# RELAY_02.net
KiCad netlist of a schematic drawn in Altium Designer
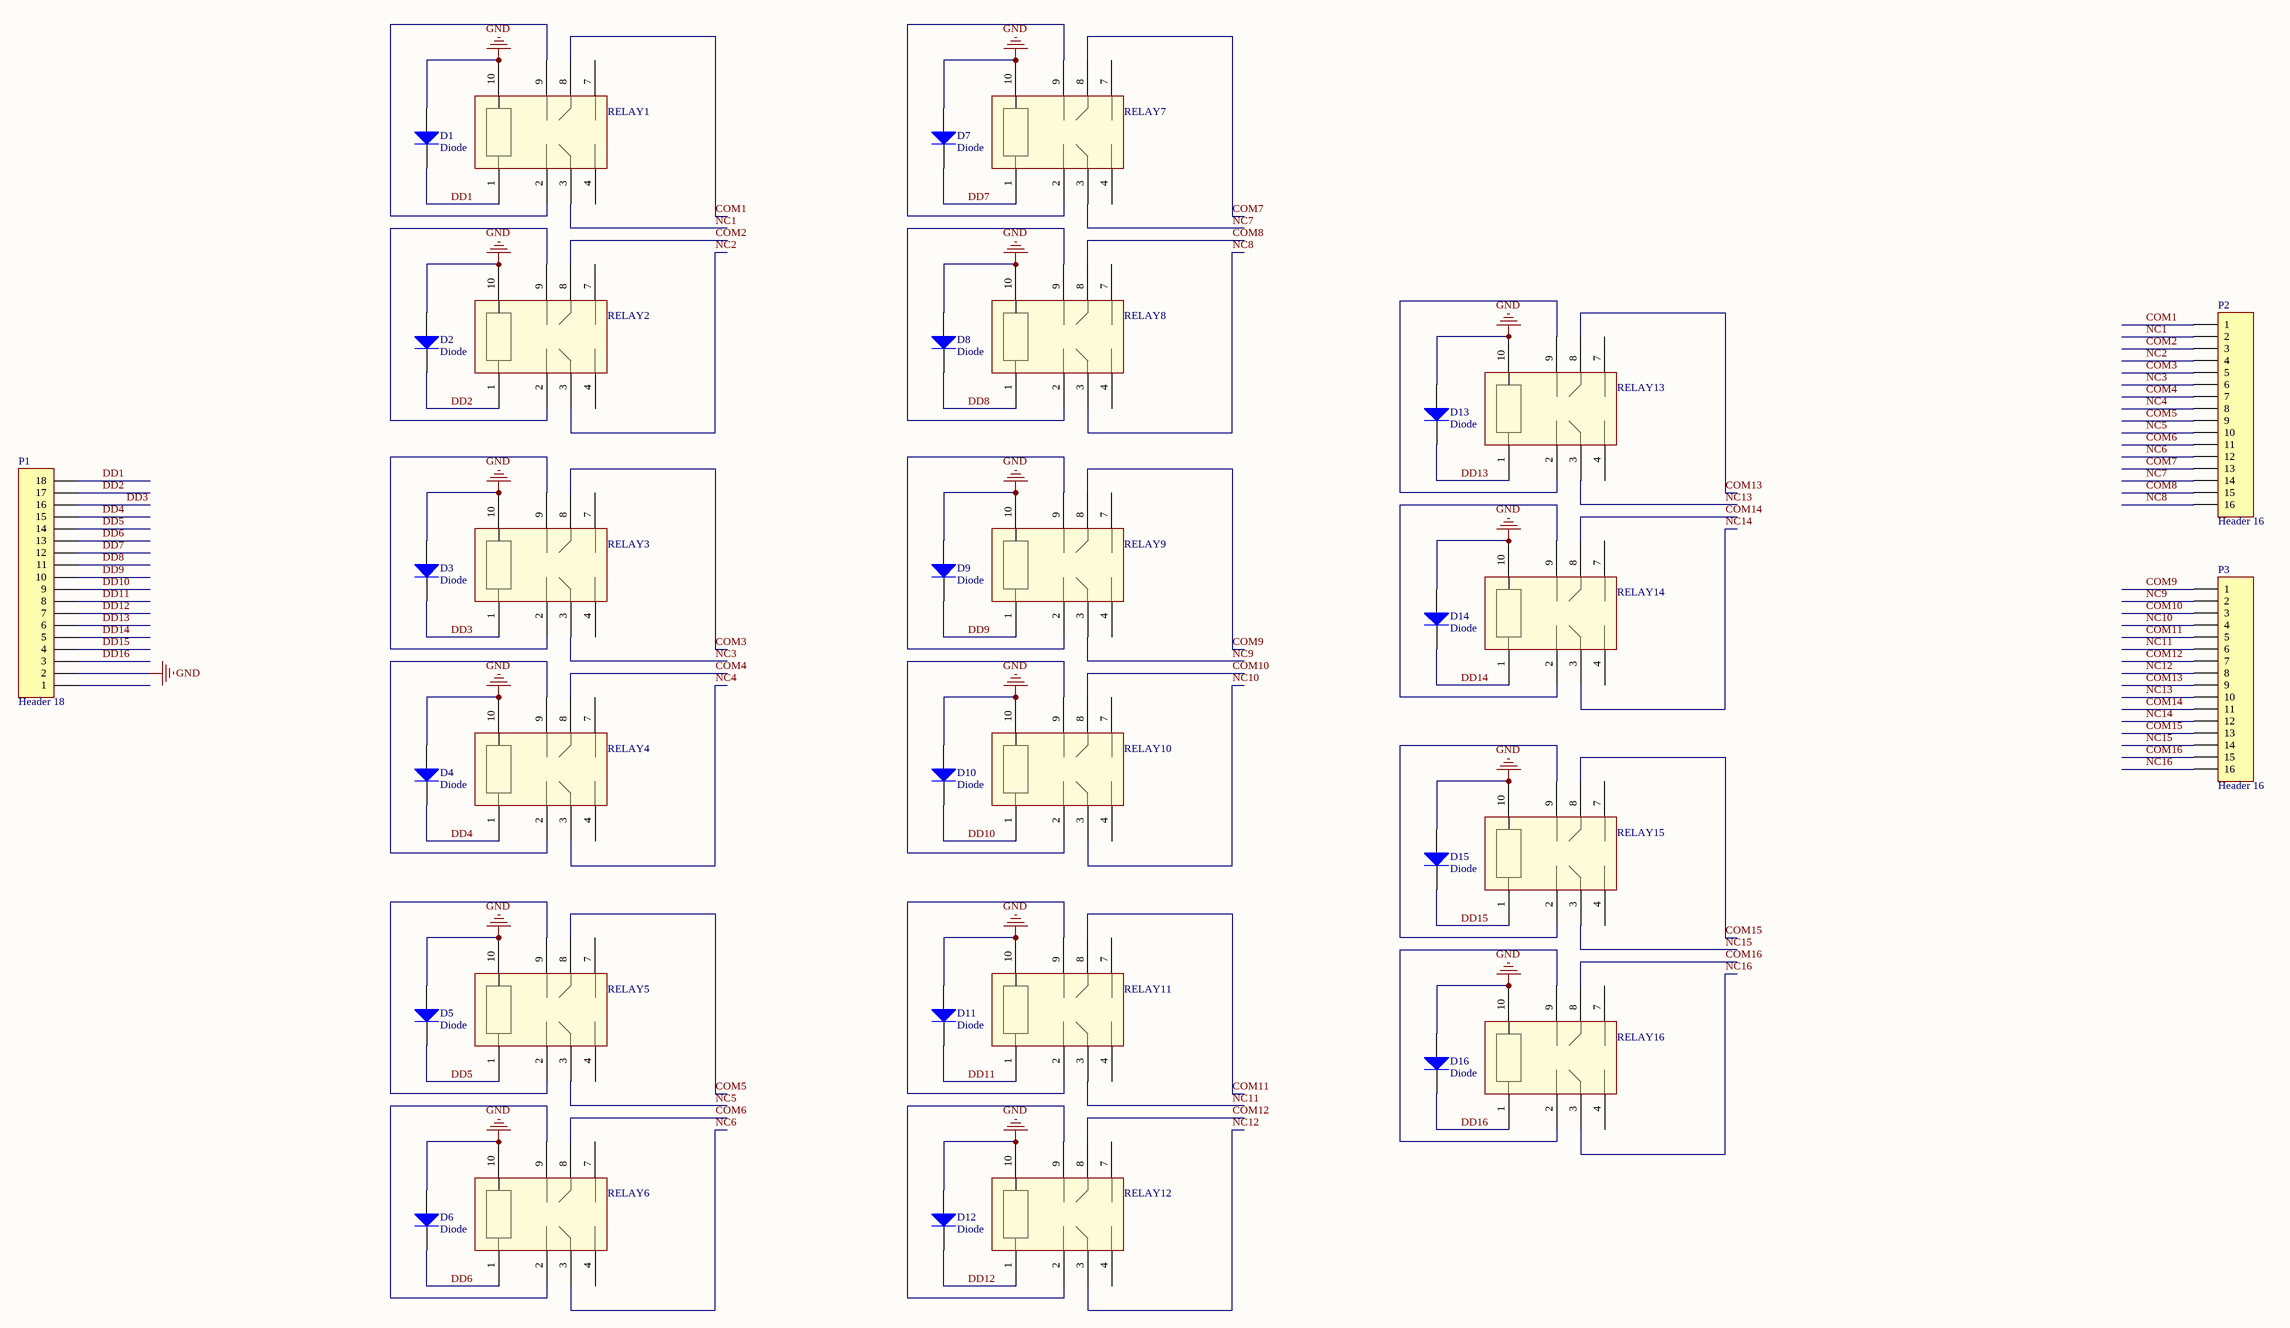
[diagram p0: RELAY 02.SchDoc]

(export (version "E")
  (design (tool "Eeschema 10.0.6"))
  (components
    (comp (ref "D1")
      (value "Diode")
      (footprint "SMB")
      (description "Default Diode")
      (fields (field (name "PUBLISHER") "Altium Limited"))
      (libsource (lib "Miscellaneous Devices") (part "Diode"))
    )
    (comp (ref "D2")
      (value "Diode")
      (footprint "SMB")
      (description "Default Diode")
      (fields (field (name "PUBLISHER") "Altium Limited"))
      (libsource (lib "Miscellaneous Devices") (part "Diode"))
    )
    (comp (ref "D3")
      (value "Diode")
      (footprint "SMB")
      (description "Default Diode")
      (fields (field (name "PUBLISHER") "Altium Limited"))
      (libsource (lib "Miscellaneous Devices") (part "Diode"))
    )
    (comp (ref "D4")
      (value "Diode")
      (footprint "SMB")
      (description "Default Diode")
      (fields (field (name "PUBLISHER") "Altium Limited"))
      (libsource (lib "Miscellaneous Devices") (part "Diode"))
    )
    (comp (ref "D5")
      (value "Diode")
      (footprint "SMB")
      (description "Default Diode")
      (fields (field (name "PUBLISHER") "Altium Limited"))
      (libsource (lib "Miscellaneous Devices") (part "Diode"))
    )
    (comp (ref "D6")
      (value "Diode")
      (footprint "SMB")
      (description "Default Diode")
      (fields (field (name "PUBLISHER") "Altium Limited"))
      (libsource (lib "Miscellaneous Devices") (part "Diode"))
    )
    (comp (ref "D7")
      (value "Diode")
      (footprint "SMB")
      (description "Default Diode")
      (fields (field (name "PUBLISHER") "Altium Limited"))
      (libsource (lib "Miscellaneous Devices") (part "Diode"))
    )
    (comp (ref "D8")
      (value "Diode")
      (footprint "SMB")
      (description "Default Diode")
      (fields (field (name "PUBLISHER") "Altium Limited"))
      (libsource (lib "Miscellaneous Devices") (part "Diode"))
    )
    (comp (ref "D9")
      (value "Diode")
      (footprint "SMB")
      (description "Default Diode")
      (fields (field (name "PUBLISHER") "Altium Limited"))
      (libsource (lib "Miscellaneous Devices") (part "Diode"))
    )
    (comp (ref "D10")
      (value "Diode")
      (footprint "SMB")
      (description "Default Diode")
      (fields (field (name "PUBLISHER") "Altium Limited"))
      (libsource (lib "Miscellaneous Devices") (part "Diode"))
    )
    (comp (ref "D11")
      (value "Diode")
      (footprint "SMB")
      (description "Default Diode")
      (fields (field (name "PUBLISHER") "Altium Limited"))
      (libsource (lib "Miscellaneous Devices") (part "Diode"))
    )
    (comp (ref "D12")
      (value "Diode")
      (footprint "SMB")
      (description "Default Diode")
      (fields (field (name "PUBLISHER") "Altium Limited"))
      (libsource (lib "Miscellaneous Devices") (part "Diode"))
    )
    (comp (ref "D13")
      (value "Diode")
      (footprint "SMB")
      (description "Default Diode")
      (fields (field (name "PUBLISHER") "Altium Limited"))
      (libsource (lib "Miscellaneous Devices") (part "Diode"))
    )
    (comp (ref "D14")
      (value "Diode")
      (footprint "SMB")
      (description "Default Diode")
      (fields (field (name "PUBLISHER") "Altium Limited"))
      (libsource (lib "Miscellaneous Devices") (part "Diode"))
    )
    (comp (ref "D15")
      (value "Diode")
      (footprint "SMB")
      (description "Default Diode")
      (fields (field (name "PUBLISHER") "Altium Limited"))
      (libsource (lib "Miscellaneous Devices") (part "Diode"))
    )
    (comp (ref "D16")
      (value "Diode")
      (footprint "SMB")
      (description "Default Diode")
      (fields (field (name "PUBLISHER") "Altium Limited"))
      (libsource (lib "Miscellaneous Devices") (part "Diode"))
    )
    (comp (ref "P1")
      (value "Header 18")
      (footprint "CON 18")
      (description "Header, 18-Pin")
      (fields (field (name "PUBLISHER") "Altium Limited"))
      (libsource (lib "Miscellaneous Connectors") (part "Header 18"))
    )
    (comp (ref "P2")
      (value "Header 16")
      (footprint "CON 16")
      (description "Header, 16-Pin")
      (fields (field (name "PUBLISHER") "Altium Limited"))
      (libsource (lib "Miscellaneous Connectors") (part "Header 16"))
    )
    (comp (ref "P3")
      (value "Header 16")
      (footprint "CON 16")
      (description "Header, 16-Pin")
      (fields (field (name "PUBLISHER") "Altium Limited"))
      (libsource (lib "Miscellaneous Connectors") (part "Header 16"))
    )
    (comp (ref "RELAY1")
      (value "OMRON RELAY")
      (footprint "G6H-2")
      (libsource (lib "dung_maker_2018") (part "OMRON G6H-2"))
    )
    (comp (ref "RELAY2")
      (value "OMRON RELAY")
      (footprint "G6H-2")
      (libsource (lib "dung_maker_2018") (part "OMRON G6H-2"))
    )
    (comp (ref "RELAY3")
      (value "OMRON RELAY")
      (footprint "G6H-2")
      (libsource (lib "dung_maker_2018") (part "OMRON G6H-2"))
    )
    (comp (ref "RELAY4")
      (value "OMRON RELAY")
      (footprint "G6H-2")
      (libsource (lib "dung_maker_2018") (part "OMRON G6H-2"))
    )
    (comp (ref "RELAY5")
      (value "OMRON RELAY")
      (footprint "G6H-2")
      (libsource (lib "dung_maker_2018") (part "OMRON G6H-2"))
    )
    (comp (ref "RELAY6")
      (value "OMRON RELAY")
      (footprint "G6H-2")
      (libsource (lib "dung_maker_2018") (part "OMRON G6H-2"))
    )
    (comp (ref "RELAY7")
      (value "OMRON RELAY")
      (footprint "G6H-2")
      (libsource (lib "dung_maker_2018") (part "OMRON G6H-2"))
    )
    (comp (ref "RELAY8")
      (value "OMRON RELAY")
      (footprint "G6H-2")
      (libsource (lib "dung_maker_2018") (part "OMRON G6H-2"))
    )
    (comp (ref "RELAY9")
      (value "OMRON RELAY")
      (footprint "G6H-2")
      (libsource (lib "dung_maker_2018") (part "OMRON G6H-2"))
    )
    (comp (ref "RELAY10")
      (value "OMRON RELAY")
      (footprint "G6H-2")
      (libsource (lib "dung_maker_2018") (part "OMRON G6H-2"))
    )
    (comp (ref "RELAY11")
      (value "OMRON RELAY")
      (footprint "G6H-2")
      (libsource (lib "dung_maker_2018") (part "OMRON G6H-2"))
    )
    (comp (ref "RELAY12")
      (value "OMRON RELAY")
      (footprint "G6H-2")
      (libsource (lib "dung_maker_2018") (part "OMRON G6H-2"))
    )
    (comp (ref "RELAY13")
      (value "OMRON RELAY")
      (footprint "G6H-2")
      (libsource (lib "dung_maker_2018") (part "OMRON G6H-2"))
    )
    (comp (ref "RELAY14")
      (value "OMRON RELAY")
      (footprint "G6H-2")
      (libsource (lib "dung_maker_2018") (part "OMRON G6H-2"))
    )
    (comp (ref "RELAY15")
      (value "OMRON RELAY")
      (footprint "G6H-2")
      (libsource (lib "dung_maker_2018") (part "OMRON G6H-2"))
    )
    (comp (ref "RELAY16")
      (value "OMRON RELAY")
      (footprint "G6H-2")
      (libsource (lib "dung_maker_2018") (part "OMRON G6H-2"))
    )
  )
  (nets
    (net (code "1") (name "/COM1") (class "Default")
      (node (ref "P2") (pin "1") (pinfunction "1_1") (pintype "passive"))
      (node (ref "RELAY1") (pin "8") (pinfunction "8_8") (pintype "passive"))
    )
    (net (code "2") (name "/COM2") (class "Default")
      (node (ref "P2") (pin "3") (pinfunction "3_3") (pintype "passive"))
      (node (ref "RELAY2") (pin "8") (pinfunction "8_8") (pintype "passive"))
    )
    (net (code "3") (name "/COM3") (class "Default")
      (node (ref "P2") (pin "5") (pinfunction "5_5") (pintype "passive"))
      (node (ref "RELAY3") (pin "8") (pinfunction "8_8") (pintype "passive"))
    )
    (net (code "4") (name "/COM4") (class "Default")
      (node (ref "P2") (pin "7") (pinfunction "7_7") (pintype "passive"))
      (node (ref "RELAY4") (pin "8") (pinfunction "8_8") (pintype "passive"))
    )
    (net (code "5") (name "/COM5") (class "Default")
      (node (ref "P2") (pin "9") (pinfunction "9_9") (pintype "passive"))
      (node (ref "RELAY5") (pin "8") (pinfunction "8_8") (pintype "passive"))
    )
    (net (code "6") (name "/COM6") (class "Default")
      (node (ref "P2") (pin "11") (pinfunction "11_11") (pintype "passive"))
      (node (ref "RELAY6") (pin "8") (pinfunction "8_8") (pintype "passive"))
    )
    (net (code "7") (name "/COM7") (class "Default")
      (node (ref "P2") (pin "13") (pinfunction "13_13") (pintype "passive"))
      (node (ref "RELAY7") (pin "8") (pinfunction "8_8") (pintype "passive"))
    )
    (net (code "8") (name "/COM8") (class "Default")
      (node (ref "P2") (pin "15") (pinfunction "15_15") (pintype "passive"))
      (node (ref "RELAY8") (pin "8") (pinfunction "8_8") (pintype "passive"))
    )
    (net (code "9") (name "/COM9") (class "Default")
      (node (ref "P3") (pin "1") (pinfunction "1_1") (pintype "passive"))
      (node (ref "RELAY9") (pin "8") (pinfunction "8_8") (pintype "passive"))
    )
    (net (code "10") (name "/COM10") (class "Default")
      (node (ref "P3") (pin "3") (pinfunction "3_3") (pintype "passive"))
      (node (ref "RELAY10") (pin "8") (pinfunction "8_8") (pintype "passive"))
    )
    (net (code "11") (name "/COM11") (class "Default")
      (node (ref "P3") (pin "5") (pinfunction "5_5") (pintype "passive"))
      (node (ref "RELAY11") (pin "8") (pinfunction "8_8") (pintype "passive"))
    )
    (net (code "12") (name "/COM12") (class "Default")
      (node (ref "P3") (pin "7") (pinfunction "7_7") (pintype "passive"))
      (node (ref "RELAY12") (pin "8") (pinfunction "8_8") (pintype "passive"))
    )
    (net (code "13") (name "/COM13") (class "Default")
      (node (ref "P3") (pin "9") (pinfunction "9_9") (pintype "passive"))
      (node (ref "RELAY13") (pin "8") (pinfunction "8_8") (pintype "passive"))
    )
    (net (code "14") (name "/COM14") (class "Default")
      (node (ref "P3") (pin "11") (pinfunction "11_11") (pintype "passive"))
      (node (ref "RELAY14") (pin "8") (pinfunction "8_8") (pintype "passive"))
    )
    (net (code "15") (name "/COM15") (class "Default")
      (node (ref "P3") (pin "13") (pinfunction "13_13") (pintype "passive"))
      (node (ref "RELAY15") (pin "8") (pinfunction "8_8") (pintype "passive"))
    )
    (net (code "16") (name "/COM16") (class "Default")
      (node (ref "P3") (pin "15") (pinfunction "15_15") (pintype "passive"))
      (node (ref "RELAY16") (pin "8") (pinfunction "8_8") (pintype "passive"))
    )
    (net (code "17") (name "/DD1") (class "Default")
      (node (ref "D1") (pin "2") (pinfunction "K_2") (pintype "passive"))
      (node (ref "P1") (pin "18") (pinfunction "18_18") (pintype "passive"))
      (node (ref "RELAY1") (pin "1") (pinfunction "1_1") (pintype "passive"))
    )
    (net (code "18") (name "/DD2") (class "Default")
      (node (ref "D2") (pin "2") (pinfunction "K_2") (pintype "passive"))
      (node (ref "P1") (pin "17") (pinfunction "17_17") (pintype "passive"))
      (node (ref "RELAY2") (pin "1") (pinfunction "1_1") (pintype "passive"))
    )
    (net (code "19") (name "/DD3") (class "Default")
      (node (ref "D3") (pin "2") (pinfunction "K_2") (pintype "passive"))
      (node (ref "P1") (pin "16") (pinfunction "16_16") (pintype "passive"))
      (node (ref "RELAY3") (pin "1") (pinfunction "1_1") (pintype "passive"))
    )
    (net (code "20") (name "/DD4") (class "Default")
      (node (ref "D4") (pin "2") (pinfunction "K_2") (pintype "passive"))
      (node (ref "P1") (pin "15") (pinfunction "15_15") (pintype "passive"))
      (node (ref "RELAY4") (pin "1") (pinfunction "1_1") (pintype "passive"))
    )
    (net (code "21") (name "/DD5") (class "Default")
      (node (ref "D5") (pin "2") (pinfunction "K_2") (pintype "passive"))
      (node (ref "P1") (pin "14") (pinfunction "14_14") (pintype "passive"))
      (node (ref "RELAY5") (pin "1") (pinfunction "1_1") (pintype "passive"))
    )
    (net (code "22") (name "/DD6") (class "Default")
      (node (ref "D6") (pin "2") (pinfunction "K_2") (pintype "passive"))
      (node (ref "P1") (pin "13") (pinfunction "13_13") (pintype "passive"))
      (node (ref "RELAY6") (pin "1") (pinfunction "1_1") (pintype "passive"))
    )
    (net (code "23") (name "/DD7") (class "Default")
      (node (ref "D7") (pin "2") (pinfunction "K_2") (pintype "passive"))
      (node (ref "P1") (pin "12") (pinfunction "12_12") (pintype "passive"))
      (node (ref "RELAY7") (pin "1") (pinfunction "1_1") (pintype "passive"))
    )
    (net (code "24") (name "/DD8") (class "Default")
      (node (ref "D8") (pin "2") (pinfunction "K_2") (pintype "passive"))
      (node (ref "P1") (pin "11") (pinfunction "11_11") (pintype "passive"))
      (node (ref "RELAY8") (pin "1") (pinfunction "1_1") (pintype "passive"))
    )
    (net (code "25") (name "/DD9") (class "Default")
      (node (ref "D9") (pin "2") (pinfunction "K_2") (pintype "passive"))
      (node (ref "P1") (pin "10") (pinfunction "10_10") (pintype "passive"))
      (node (ref "RELAY9") (pin "1") (pinfunction "1_1") (pintype "passive"))
    )
    (net (code "26") (name "/DD10") (class "Default")
      (node (ref "D10") (pin "2") (pinfunction "K_2") (pintype "passive"))
      (node (ref "P1") (pin "9") (pinfunction "9_9") (pintype "passive"))
      (node (ref "RELAY10") (pin "1") (pinfunction "1_1") (pintype "passive"))
    )
    (net (code "27") (name "/DD11") (class "Default")
      (node (ref "D11") (pin "2") (pinfunction "K_2") (pintype "passive"))
      (node (ref "P1") (pin "8") (pinfunction "8_8") (pintype "passive"))
      (node (ref "RELAY11") (pin "1") (pinfunction "1_1") (pintype "passive"))
    )
    (net (code "28") (name "/DD12") (class "Default")
      (node (ref "D12") (pin "2") (pinfunction "K_2") (pintype "passive"))
      (node (ref "P1") (pin "7") (pinfunction "7_7") (pintype "passive"))
      (node (ref "RELAY12") (pin "1") (pinfunction "1_1") (pintype "passive"))
    )
    (net (code "29") (name "/DD13") (class "Default")
      (node (ref "D13") (pin "2") (pinfunction "K_2") (pintype "passive"))
      (node (ref "P1") (pin "6") (pinfunction "6_6") (pintype "passive"))
      (node (ref "RELAY13") (pin "1") (pinfunction "1_1") (pintype "passive"))
    )
    (net (code "30") (name "/DD14") (class "Default")
      (node (ref "D14") (pin "2") (pinfunction "K_2") (pintype "passive"))
      (node (ref "P1") (pin "5") (pinfunction "5_5") (pintype "passive"))
      (node (ref "RELAY14") (pin "1") (pinfunction "1_1") (pintype "passive"))
    )
    (net (code "31") (name "/DD15") (class "Default")
      (node (ref "D15") (pin "2") (pinfunction "K_2") (pintype "passive"))
      (node (ref "P1") (pin "4") (pinfunction "4_4") (pintype "passive"))
      (node (ref "RELAY15") (pin "1") (pinfunction "1_1") (pintype "passive"))
    )
    (net (code "32") (name "/DD16") (class "Default")
      (node (ref "D16") (pin "2") (pinfunction "K_2") (pintype "passive"))
      (node (ref "P1") (pin "3") (pinfunction "3_3") (pintype "passive"))
      (node (ref "RELAY16") (pin "1") (pinfunction "1_1") (pintype "passive"))
    )
    (net (code "33") (name "/NC1") (class "Default")
      (node (ref "P2") (pin "2") (pinfunction "2_2") (pintype "passive"))
      (node (ref "RELAY1") (pin "3") (pinfunction "3_3") (pintype "passive"))
    )
    (net (code "34") (name "/NC2") (class "Default")
      (node (ref "P2") (pin "4") (pinfunction "4_4") (pintype "passive"))
      (node (ref "RELAY2") (pin "3") (pinfunction "3_3") (pintype "passive"))
    )
    (net (code "35") (name "/NC3") (class "Default")
      (node (ref "P2") (pin "6") (pinfunction "6_6") (pintype "passive"))
      (node (ref "RELAY3") (pin "3") (pinfunction "3_3") (pintype "passive"))
    )
    (net (code "36") (name "/NC4") (class "Default")
      (node (ref "P2") (pin "8") (pinfunction "8_8") (pintype "passive"))
      (node (ref "RELAY4") (pin "3") (pinfunction "3_3") (pintype "passive"))
    )
    (net (code "37") (name "/NC5") (class "Default")
      (node (ref "P2") (pin "10") (pinfunction "10_10") (pintype "passive"))
      (node (ref "RELAY5") (pin "3") (pinfunction "3_3") (pintype "passive"))
    )
    (net (code "38") (name "/NC6") (class "Default")
      (node (ref "P2") (pin "12") (pinfunction "12_12") (pintype "passive"))
      (node (ref "RELAY6") (pin "3") (pinfunction "3_3") (pintype "passive"))
    )
    (net (code "39") (name "/NC7") (class "Default")
      (node (ref "P2") (pin "14") (pinfunction "14_14") (pintype "passive"))
      (node (ref "RELAY7") (pin "3") (pinfunction "3_3") (pintype "passive"))
    )
    (net (code "40") (name "/NC8") (class "Default")
      (node (ref "P2") (pin "16") (pinfunction "16_16") (pintype "passive"))
      (node (ref "RELAY8") (pin "3") (pinfunction "3_3") (pintype "passive"))
    )
    (net (code "41") (name "/NC9") (class "Default")
      (node (ref "P3") (pin "2") (pinfunction "2_2") (pintype "passive"))
      (node (ref "RELAY9") (pin "3") (pinfunction "3_3") (pintype "passive"))
    )
    (net (code "42") (name "/NC10") (class "Default")
      (node (ref "P3") (pin "4") (pinfunction "4_4") (pintype "passive"))
      (node (ref "RELAY10") (pin "3") (pinfunction "3_3") (pintype "passive"))
    )
    (net (code "43") (name "/NC11") (class "Default")
      (node (ref "P3") (pin "6") (pinfunction "6_6") (pintype "passive"))
      (node (ref "RELAY11") (pin "3") (pinfunction "3_3") (pintype "passive"))
    )
    (net (code "44") (name "/NC12") (class "Default")
      (node (ref "P3") (pin "8") (pinfunction "8_8") (pintype "passive"))
      (node (ref "RELAY12") (pin "3") (pinfunction "3_3") (pintype "passive"))
    )
    (net (code "45") (name "/NC13") (class "Default")
      (node (ref "P3") (pin "10") (pinfunction "10_10") (pintype "passive"))
      (node (ref "RELAY13") (pin "3") (pinfunction "3_3") (pintype "passive"))
    )
    (net (code "46") (name "/NC14") (class "Default")
      (node (ref "P3") (pin "12") (pinfunction "12_12") (pintype "passive"))
      (node (ref "RELAY14") (pin "3") (pinfunction "3_3") (pintype "passive"))
    )
    (net (code "47") (name "/NC15") (class "Default")
      (node (ref "P3") (pin "14") (pinfunction "14_14") (pintype "passive"))
      (node (ref "RELAY15") (pin "3") (pinfunction "3_3") (pintype "passive"))
    )
    (net (code "48") (name "/NC16") (class "Default")
      (node (ref "P3") (pin "16") (pinfunction "16_16") (pintype "passive"))
      (node (ref "RELAY16") (pin "3") (pinfunction "3_3") (pintype "passive"))
    )
    (net (code "49") (name "GND") (class "Default")
      (node (ref "D1") (pin "1") (pinfunction "A_1") (pintype "passive"))
      (node (ref "D10") (pin "1") (pinfunction "A_1") (pintype "passive"))
      (node (ref "D11") (pin "1") (pinfunction "A_1") (pintype "passive"))
      (node (ref "D12") (pin "1") (pinfunction "A_1") (pintype "passive"))
      (node (ref "D13") (pin "1") (pinfunction "A_1") (pintype "passive"))
      (node (ref "D14") (pin "1") (pinfunction "A_1") (pintype "passive"))
      (node (ref "D15") (pin "1") (pinfunction "A_1") (pintype "passive"))
      (node (ref "D16") (pin "1") (pinfunction "A_1") (pintype "passive"))
      (node (ref "D2") (pin "1") (pinfunction "A_1") (pintype "passive"))
      (node (ref "D3") (pin "1") (pinfunction "A_1") (pintype "passive"))
      (node (ref "D4") (pin "1") (pinfunction "A_1") (pintype "passive"))
      (node (ref "D5") (pin "1") (pinfunction "A_1") (pintype "passive"))
      (node (ref "D6") (pin "1") (pinfunction "A_1") (pintype "passive"))
      (node (ref "D7") (pin "1") (pinfunction "A_1") (pintype "passive"))
      (node (ref "D8") (pin "1") (pinfunction "A_1") (pintype "passive"))
      (node (ref "D9") (pin "1") (pinfunction "A_1") (pintype "passive"))
      (node (ref "P1") (pin "2") (pinfunction "2_2") (pintype "passive"))
      (node (ref "RELAY1") (pin "10") (pinfunction "10_10") (pintype "passive"))
      (node (ref "RELAY10") (pin "10") (pinfunction "10_10") (pintype "passive"))
      (node (ref "RELAY11") (pin "10") (pinfunction "10_10") (pintype "passive"))
      (node (ref "RELAY12") (pin "10") (pinfunction "10_10") (pintype "passive"))
      (node (ref "RELAY13") (pin "10") (pinfunction "10_10") (pintype "passive"))
      (node (ref "RELAY14") (pin "10") (pinfunction "10_10") (pintype "passive"))
      (node (ref "RELAY15") (pin "10") (pinfunction "10_10") (pintype "passive"))
      (node (ref "RELAY16") (pin "10") (pinfunction "10_10") (pintype "passive"))
      (node (ref "RELAY2") (pin "10") (pinfunction "10_10") (pintype "passive"))
      (node (ref "RELAY3") (pin "10") (pinfunction "10_10") (pintype "passive"))
      (node (ref "RELAY4") (pin "10") (pinfunction "10_10") (pintype "passive"))
      (node (ref "RELAY5") (pin "10") (pinfunction "10_10") (pintype "passive"))
      (node (ref "RELAY6") (pin "10") (pinfunction "10_10") (pintype "passive"))
      (node (ref "RELAY7") (pin "10") (pinfunction "10_10") (pintype "passive"))
      (node (ref "RELAY8") (pin "10") (pinfunction "10_10") (pintype "passive"))
      (node (ref "RELAY9") (pin "10") (pinfunction "10_10") (pintype "passive"))
    )
    (net (code "50") (name "Net-(RELAY1-Pad2)") (class "Default")
      (node (ref "RELAY1") (pin "2") (pinfunction "2_2") (pintype "passive"))
      (node (ref "RELAY1") (pin "9") (pinfunction "9_9") (pintype "passive"))
    )
    (net (code "51") (name "Net-(RELAY2-Pad2)") (class "Default")
      (node (ref "RELAY2") (pin "2") (pinfunction "2_2") (pintype "passive"))
      (node (ref "RELAY2") (pin "9") (pinfunction "9_9") (pintype "passive"))
    )
    (net (code "52") (name "Net-(RELAY3-Pad2)") (class "Default")
      (node (ref "RELAY3") (pin "2") (pinfunction "2_2") (pintype "passive"))
      (node (ref "RELAY3") (pin "9") (pinfunction "9_9") (pintype "passive"))
    )
    (net (code "53") (name "Net-(RELAY4-Pad2)") (class "Default")
      (node (ref "RELAY4") (pin "2") (pinfunction "2_2") (pintype "passive"))
      (node (ref "RELAY4") (pin "9") (pinfunction "9_9") (pintype "passive"))
    )
    (net (code "54") (name "Net-(RELAY5-Pad2)") (class "Default")
      (node (ref "RELAY5") (pin "2") (pinfunction "2_2") (pintype "passive"))
      (node (ref "RELAY5") (pin "9") (pinfunction "9_9") (pintype "passive"))
    )
    (net (code "55") (name "Net-(RELAY6-Pad2)") (class "Default")
      (node (ref "RELAY6") (pin "2") (pinfunction "2_2") (pintype "passive"))
      (node (ref "RELAY6") (pin "9") (pinfunction "9_9") (pintype "passive"))
    )
    (net (code "56") (name "Net-(RELAY7-Pad2)") (class "Default")
      (node (ref "RELAY7") (pin "2") (pinfunction "2_2") (pintype "passive"))
      (node (ref "RELAY7") (pin "9") (pinfunction "9_9") (pintype "passive"))
    )
    (net (code "57") (name "Net-(RELAY8-Pad2)") (class "Default")
      (node (ref "RELAY8") (pin "2") (pinfunction "2_2") (pintype "passive"))
      (node (ref "RELAY8") (pin "9") (pinfunction "9_9") (pintype "passive"))
    )
    (net (code "58") (name "Net-(RELAY9-Pad2)") (class "Default")
      (node (ref "RELAY9") (pin "2") (pinfunction "2_2") (pintype "passive"))
      (node (ref "RELAY9") (pin "9") (pinfunction "9_9") (pintype "passive"))
    )
    (net (code "59") (name "Net-(RELAY10-Pad2)") (class "Default")
      (node (ref "RELAY10") (pin "2") (pinfunction "2_2") (pintype "passive"))
      (node (ref "RELAY10") (pin "9") (pinfunction "9_9") (pintype "passive"))
    )
    (net (code "60") (name "Net-(RELAY11-Pad2)") (class "Default")
      (node (ref "RELAY11") (pin "2") (pinfunction "2_2") (pintype "passive"))
      (node (ref "RELAY11") (pin "9") (pinfunction "9_9") (pintype "passive"))
    )
    (net (code "61") (name "Net-(RELAY12-Pad2)") (class "Default")
      (node (ref "RELAY12") (pin "2") (pinfunction "2_2") (pintype "passive"))
      (node (ref "RELAY12") (pin "9") (pinfunction "9_9") (pintype "passive"))
    )
    (net (code "62") (name "Net-(RELAY13-Pad2)") (class "Default")
      (node (ref "RELAY13") (pin "2") (pinfunction "2_2") (pintype "passive"))
      (node (ref "RELAY13") (pin "9") (pinfunction "9_9") (pintype "passive"))
    )
    (net (code "63") (name "Net-(RELAY14-Pad2)") (class "Default")
      (node (ref "RELAY14") (pin "2") (pinfunction "2_2") (pintype "passive"))
      (node (ref "RELAY14") (pin "9") (pinfunction "9_9") (pintype "passive"))
    )
    (net (code "64") (name "Net-(RELAY15-Pad2)") (class "Default")
      (node (ref "RELAY15") (pin "2") (pinfunction "2_2") (pintype "passive"))
      (node (ref "RELAY15") (pin "9") (pinfunction "9_9") (pintype "passive"))
    )
    (net (code "65") (name "Net-(RELAY16-Pad2)") (class "Default")
      (node (ref "RELAY16") (pin "2") (pinfunction "2_2") (pintype "passive"))
      (node (ref "RELAY16") (pin "9") (pinfunction "9_9") (pintype "passive"))
    )
    (net (code "66") (name "unconnected-(P1-Pad1)") (class "Default")
      (node (ref "P1") (pin "1") (pinfunction "1_1") (pintype "passive"))
    )
    (net (code "67") (name "unconnected-(RELAY1-Pad4)") (class "Default")
      (node (ref "RELAY1") (pin "4") (pinfunction "4_4") (pintype "passive"))
    )
    (net (code "68") (name "unconnected-(RELAY1-Pad5)") (class "Default")
      (node (ref "RELAY1") (pin "5") (pinfunction "5_5") (pintype "passive"))
    )
    (net (code "69") (name "unconnected-(RELAY1-Pad6)") (class "Default")
      (node (ref "RELAY1") (pin "6") (pinfunction "6_6") (pintype "passive"))
    )
    (net (code "70") (name "unconnected-(RELAY1-Pad7)") (class "Default")
      (node (ref "RELAY1") (pin "7") (pinfunction "7_7") (pintype "passive"))
    )
    (net (code "71") (name "unconnected-(RELAY2-Pad4)") (class "Default")
      (node (ref "RELAY2") (pin "4") (pinfunction "4_4") (pintype "passive"))
    )
    (net (code "72") (name "unconnected-(RELAY2-Pad5)") (class "Default")
      (node (ref "RELAY2") (pin "5") (pinfunction "5_5") (pintype "passive"))
    )
    (net (code "73") (name "unconnected-(RELAY2-Pad6)") (class "Default")
      (node (ref "RELAY2") (pin "6") (pinfunction "6_6") (pintype "passive"))
    )
    (net (code "74") (name "unconnected-(RELAY2-Pad7)") (class "Default")
      (node (ref "RELAY2") (pin "7") (pinfunction "7_7") (pintype "passive"))
    )
    (net (code "75") (name "unconnected-(RELAY3-Pad4)") (class "Default")
      (node (ref "RELAY3") (pin "4") (pinfunction "4_4") (pintype "passive"))
    )
    (net (code "76") (name "unconnected-(RELAY3-Pad5)") (class "Default")
      (node (ref "RELAY3") (pin "5") (pinfunction "5_5") (pintype "passive"))
    )
    (net (code "77") (name "unconnected-(RELAY3-Pad6)") (class "Default")
      (node (ref "RELAY3") (pin "6") (pinfunction "6_6") (pintype "passive"))
    )
    (net (code "78") (name "unconnected-(RELAY3-Pad7)") (class "Default")
      (node (ref "RELAY3") (pin "7") (pinfunction "7_7") (pintype "passive"))
    )
    (net (code "79") (name "unconnected-(RELAY4-Pad4)") (class "Default")
      (node (ref "RELAY4") (pin "4") (pinfunction "4_4") (pintype "passive"))
    )
    (net (code "80") (name "unconnected-(RELAY4-Pad5)") (class "Default")
      (node (ref "RELAY4") (pin "5") (pinfunction "5_5") (pintype "passive"))
    )
    (net (code "81") (name "unconnected-(RELAY4-Pad6)") (class "Default")
      (node (ref "RELAY4") (pin "6") (pinfunction "6_6") (pintype "passive"))
    )
    (net (code "82") (name "unconnected-(RELAY4-Pad7)") (class "Default")
      (node (ref "RELAY4") (pin "7") (pinfunction "7_7") (pintype "passive"))
    )
    (net (code "83") (name "unconnected-(RELAY5-Pad4)") (class "Default")
      (node (ref "RELAY5") (pin "4") (pinfunction "4_4") (pintype "passive"))
    )
    (net (code "84") (name "unconnected-(RELAY5-Pad5)") (class "Default")
      (node (ref "RELAY5") (pin "5") (pinfunction "5_5") (pintype "passive"))
    )
    (net (code "85") (name "unconnected-(RELAY5-Pad6)") (class "Default")
      (node (ref "RELAY5") (pin "6") (pinfunction "6_6") (pintype "passive"))
    )
    (net (code "86") (name "unconnected-(RELAY5-Pad7)") (class "Default")
      (node (ref "RELAY5") (pin "7") (pinfunction "7_7") (pintype "passive"))
    )
    (net (code "87") (name "unconnected-(RELAY6-Pad4)") (class "Default")
      (node (ref "RELAY6") (pin "4") (pinfunction "4_4") (pintype "passive"))
    )
    (net (code "88") (name "unconnected-(RELAY6-Pad5)") (class "Default")
      (node (ref "RELAY6") (pin "5") (pinfunction "5_5") (pintype "passive"))
    )
    (net (code "89") (name "unconnected-(RELAY6-Pad6)") (class "Default")
      (node (ref "RELAY6") (pin "6") (pinfunction "6_6") (pintype "passive"))
    )
    (net (code "90") (name "unconnected-(RELAY6-Pad7)") (class "Default")
      (node (ref "RELAY6") (pin "7") (pinfunction "7_7") (pintype "passive"))
    )
    (net (code "91") (name "unconnected-(RELAY7-Pad4)") (class "Default")
      (node (ref "RELAY7") (pin "4") (pinfunction "4_4") (pintype "passive"))
    )
    (net (code "92") (name "unconnected-(RELAY7-Pad5)") (class "Default")
      (node (ref "RELAY7") (pin "5") (pinfunction "5_5") (pintype "passive"))
    )
    (net (code "93") (name "unconnected-(RELAY7-Pad6)") (class "Default")
      (node (ref "RELAY7") (pin "6") (pinfunction "6_6") (pintype "passive"))
    )
    (net (code "94") (name "unconnected-(RELAY7-Pad7)") (class "Default")
      (node (ref "RELAY7") (pin "7") (pinfunction "7_7") (pintype "passive"))
    )
    (net (code "95") (name "unconnected-(RELAY8-Pad4)") (class "Default")
      (node (ref "RELAY8") (pin "4") (pinfunction "4_4") (pintype "passive"))
    )
    (net (code "96") (name "unconnected-(RELAY8-Pad5)") (class "Default")
      (node (ref "RELAY8") (pin "5") (pinfunction "5_5") (pintype "passive"))
    )
    (net (code "97") (name "unconnected-(RELAY8-Pad6)") (class "Default")
      (node (ref "RELAY8") (pin "6") (pinfunction "6_6") (pintype "passive"))
    )
    (net (code "98") (name "unconnected-(RELAY8-Pad7)") (class "Default")
      (node (ref "RELAY8") (pin "7") (pinfunction "7_7") (pintype "passive"))
    )
    (net (code "99") (name "unconnected-(RELAY9-Pad4)") (class "Default")
      (node (ref "RELAY9") (pin "4") (pinfunction "4_4") (pintype "passive"))
    )
    (net (code "100") (name "unconnected-(RELAY9-Pad5)") (class "Default")
      (node (ref "RELAY9") (pin "5") (pinfunction "5_5") (pintype "passive"))
    )
    (net (code "101") (name "unconnected-(RELAY9-Pad6)") (class "Default")
      (node (ref "RELAY9") (pin "6") (pinfunction "6_6") (pintype "passive"))
    )
    (net (code "102") (name "unconnected-(RELAY9-Pad7)") (class "Default")
      (node (ref "RELAY9") (pin "7") (pinfunction "7_7") (pintype "passive"))
    )
    (net (code "103") (name "unconnected-(RELAY10-Pad4)") (class "Default")
      (node (ref "RELAY10") (pin "4") (pinfunction "4_4") (pintype "passive"))
    )
    (net (code "104") (name "unconnected-(RELAY10-Pad5)") (class "Default")
      (node (ref "RELAY10") (pin "5") (pinfunction "5_5") (pintype "passive"))
    )
    (net (code "105") (name "unconnected-(RELAY10-Pad6)") (class "Default")
      (node (ref "RELAY10") (pin "6") (pinfunction "6_6") (pintype "passive"))
    )
    (net (code "106") (name "unconnected-(RELAY10-Pad7)") (class "Default")
      (node (ref "RELAY10") (pin "7") (pinfunction "7_7") (pintype "passive"))
    )
    (net (code "107") (name "unconnected-(RELAY11-Pad4)") (class "Default")
      (node (ref "RELAY11") (pin "4") (pinfunction "4_4") (pintype "passive"))
    )
    (net (code "108") (name "unconnected-(RELAY11-Pad5)") (class "Default")
      (node (ref "RELAY11") (pin "5") (pinfunction "5_5") (pintype "passive"))
    )
    (net (code "109") (name "unconnected-(RELAY11-Pad6)") (class "Default")
      (node (ref "RELAY11") (pin "6") (pinfunction "6_6") (pintype "passive"))
    )
    (net (code "110") (name "unconnected-(RELAY11-Pad7)") (class "Default")
      (node (ref "RELAY11") (pin "7") (pinfunction "7_7") (pintype "passive"))
    )
    (net (code "111") (name "unconnected-(RELAY12-Pad4)") (class "Default")
      (node (ref "RELAY12") (pin "4") (pinfunction "4_4") (pintype "passive"))
    )
    (net (code "112") (name "unconnected-(RELAY12-Pad5)") (class "Default")
      (node (ref "RELAY12") (pin "5") (pinfunction "5_5") (pintype "passive"))
    )
    (net (code "113") (name "unconnected-(RELAY12-Pad6)") (class "Default")
      (node (ref "RELAY12") (pin "6") (pinfunction "6_6") (pintype "passive"))
    )
    (net (code "114") (name "unconnected-(RELAY12-Pad7)") (class "Default")
      (node (ref "RELAY12") (pin "7") (pinfunction "7_7") (pintype "passive"))
    )
    (net (code "115") (name "unconnected-(RELAY13-Pad4)") (class "Default")
      (node (ref "RELAY13") (pin "4") (pinfunction "4_4") (pintype "passive"))
    )
    (net (code "116") (name "unconnected-(RELAY13-Pad5)") (class "Default")
      (node (ref "RELAY13") (pin "5") (pinfunction "5_5") (pintype "passive"))
    )
    (net (code "117") (name "unconnected-(RELAY13-Pad6)") (class "Default")
      (node (ref "RELAY13") (pin "6") (pinfunction "6_6") (pintype "passive"))
    )
    (net (code "118") (name "unconnected-(RELAY13-Pad7)") (class "Default")
      (node (ref "RELAY13") (pin "7") (pinfunction "7_7") (pintype "passive"))
    )
    (net (code "119") (name "unconnected-(RELAY14-Pad4)") (class "Default")
      (node (ref "RELAY14") (pin "4") (pinfunction "4_4") (pintype "passive"))
    )
    (net (code "120") (name "unconnected-(RELAY14-Pad5)") (class "Default")
      (node (ref "RELAY14") (pin "5") (pinfunction "5_5") (pintype "passive"))
    )
    (net (code "121") (name "unconnected-(RELAY14-Pad6)") (class "Default")
      (node (ref "RELAY14") (pin "6") (pinfunction "6_6") (pintype "passive"))
    )
    (net (code "122") (name "unconnected-(RELAY14-Pad7)") (class "Default")
      (node (ref "RELAY14") (pin "7") (pinfunction "7_7") (pintype "passive"))
    )
    (net (code "123") (name "unconnected-(RELAY15-Pad4)") (class "Default")
      (node (ref "RELAY15") (pin "4") (pinfunction "4_4") (pintype "passive"))
    )
    (net (code "124") (name "unconnected-(RELAY15-Pad5)") (class "Default")
      (node (ref "RELAY15") (pin "5") (pinfunction "5_5") (pintype "passive"))
    )
    (net (code "125") (name "unconnected-(RELAY15-Pad6)") (class "Default")
      (node (ref "RELAY15") (pin "6") (pinfunction "6_6") (pintype "passive"))
    )
    (net (code "126") (name "unconnected-(RELAY15-Pad7)") (class "Default")
      (node (ref "RELAY15") (pin "7") (pinfunction "7_7") (pintype "passive"))
    )
    (net (code "127") (name "unconnected-(RELAY16-Pad4)") (class "Default")
      (node (ref "RELAY16") (pin "4") (pinfunction "4_4") (pintype "passive"))
    )
    (net (code "128") (name "unconnected-(RELAY16-Pad5)") (class "Default")
      (node (ref "RELAY16") (pin "5") (pinfunction "5_5") (pintype "passive"))
    )
    (net (code "129") (name "unconnected-(RELAY16-Pad6)") (class "Default")
      (node (ref "RELAY16") (pin "6") (pinfunction "6_6") (pintype "passive"))
    )
    (net (code "130") (name "unconnected-(RELAY16-Pad7)") (class "Default")
      (node (ref "RELAY16") (pin "7") (pinfunction "7_7") (pintype "passive"))
    )
  )
)
